# BareBonesArduino.net
KiCad netlist of a schematic drawn in EAGLE
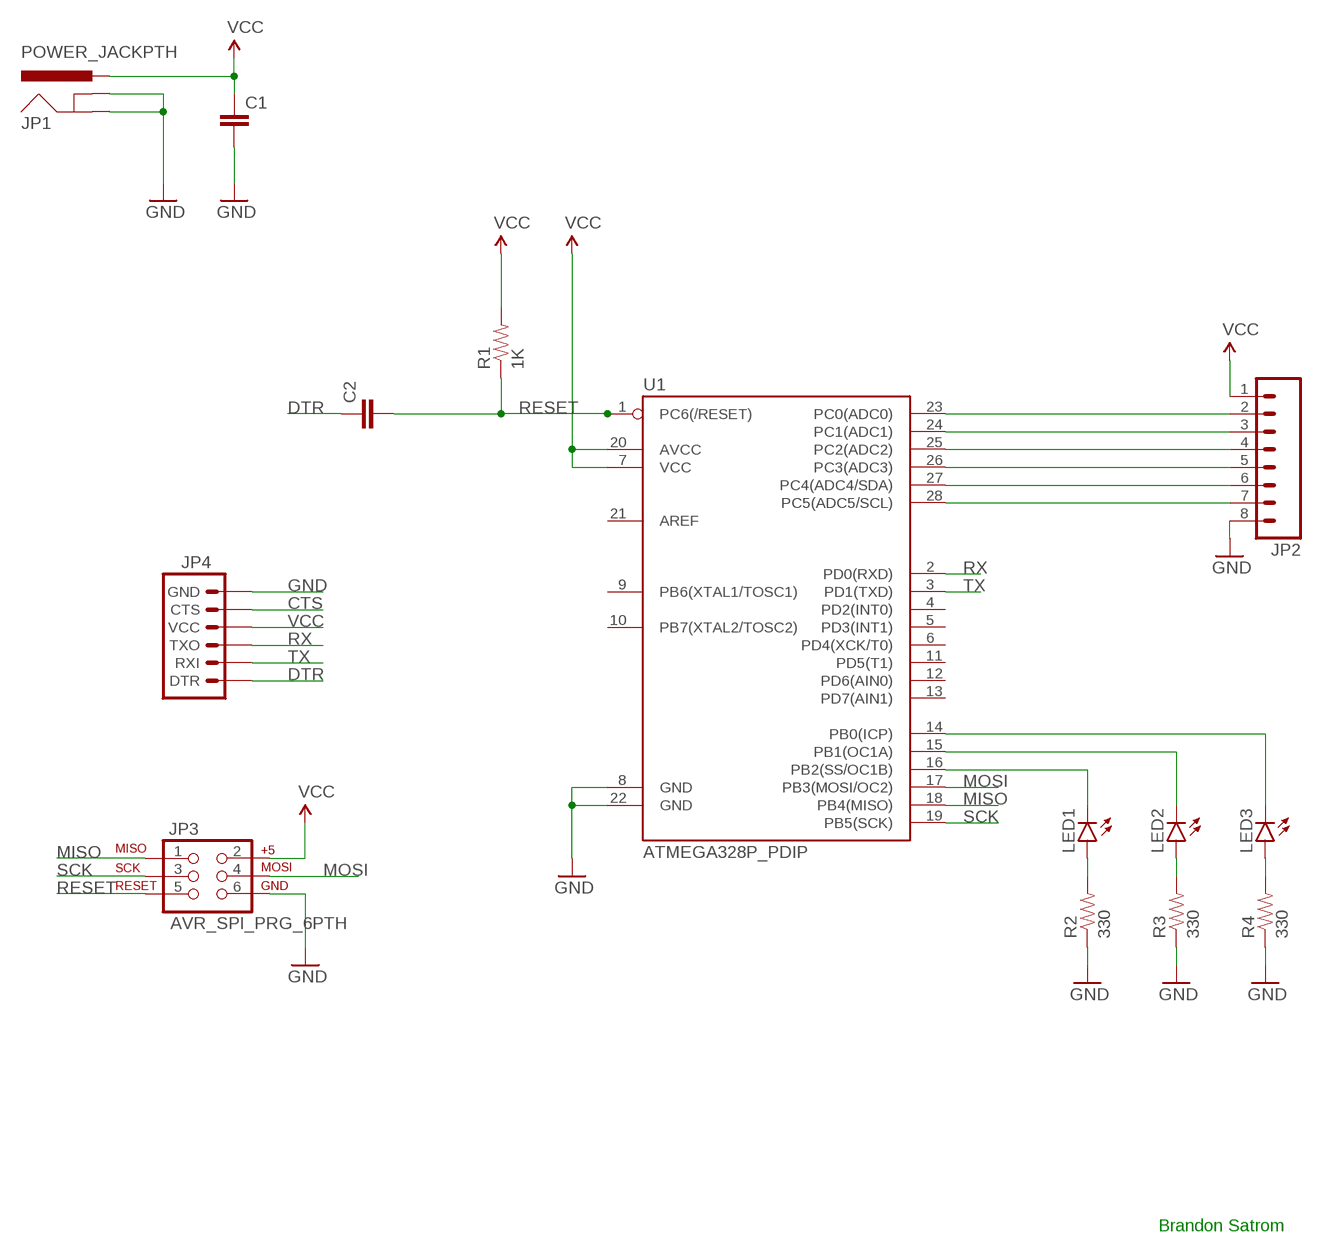
[diagram p0: schematic, sheet 1]

(export (version "E")
  (design (tool "Eeschema 10.0.6"))
  (components
    (comp (ref "C1")
      (value "CAPPTH")
      (footprint "eagle-import:CAP-PTH-SMALL")
      (libsource (lib "eagle-import") (part "CAPPTH"))
    )
    (comp (ref "C2")
      (value "CAPPTH")
      (footprint "eagle-import:CAP-PTH-SMALL")
      (libsource (lib "eagle-import") (part "CAPPTH"))
    )
    (comp (ref "JP1")
      (value "POWER_JACKPTH")
      (footprint "eagle-import:POWER_JACK_PTH")
      (libsource (lib "eagle-import") (part "POWER_JACKPTH"))
    )
    (comp (ref "JP2")
      (value "M08")
      (footprint "eagle-import:1X08_ROUND")
      (libsource (lib "eagle-import") (part "M08"))
    )
    (comp (ref "JP3")
      (value "AVR_SPI_PRG_6PTH")
      (footprint "eagle-import:2X3")
      (libsource (lib "eagle-import") (part "AVR_SPI_PRG_6PTH"))
    )
    (comp (ref "JP4")
      (value "ARDUINO_SERIAL_PROGRAMPTH")
      (footprint "eagle-import:1X06")
      (libsource (lib "eagle-import") (part "ARDUINO_SERIAL_PROGRAMPTH"))
    )
    (comp (ref "LED1")
      (value "LED5MM")
      (footprint "eagle-import:LED5MM")
      (libsource (lib "eagle-import") (part "LED5MM"))
    )
    (comp (ref "LED2")
      (value "LED5MM")
      (footprint "eagle-import:LED5MM")
      (libsource (lib "eagle-import") (part "LED5MM"))
    )
    (comp (ref "LED3")
      (value "LED5MM")
      (footprint "eagle-import:LED5MM")
      (libsource (lib "eagle-import") (part "LED5MM"))
    )
    (comp (ref "R1")
      (value "1K")
      (footprint "eagle-import:AXIAL-0.4")
      (libsource (lib "eagle-import") (part "RESISTORPTH-1/4W"))
    )
    (comp (ref "R2")
      (value "330")
      (footprint "eagle-import:AXIAL-0.4")
      (libsource (lib "eagle-import") (part "RESISTORPTH-1/4W"))
    )
    (comp (ref "R3")
      (value "330")
      (footprint "eagle-import:AXIAL-0.4")
      (libsource (lib "eagle-import") (part "RESISTORPTH-1/4W"))
    )
    (comp (ref "R4")
      (value "330")
      (footprint "eagle-import:AXIAL-0.4")
      (libsource (lib "eagle-import") (part "RESISTORPTH-1/4W"))
    )
    (comp (ref "U1")
      (value "ATMEGA328P_PDIP")
      (footprint "eagle-import:DIL28-3")
      (libsource (lib "eagle-import") (part "ATMEGA328P_PDIP"))
    )
  )
  (nets
    (net (code "1") (name "/CTS") (class "Default")
      (node (ref "JP4") (pin "5") (pinfunction "CTS_5") (pintype "passive"))
    )
    (net (code "2") (name "/DTR") (class "Default")
      (node (ref "C2") (pin "1") (pinfunction "1_1") (pintype "passive"))
      (node (ref "JP4") (pin "1") (pinfunction "DTR_1") (pintype "passive"))
    )
    (net (code "3") (name "/MISO") (class "Default")
      (node (ref "JP3") (pin "1") (pinfunction "1_1") (pintype "passive"))
      (node (ref "U1") (pin "18") (pinfunction "PB4(MISO)_18") (pintype "bidirectional"))
    )
    (net (code "4") (name "/MOSI") (class "Default")
      (node (ref "JP3") (pin "4") (pinfunction "4_4") (pintype "passive"))
      (node (ref "U1") (pin "17") (pinfunction "PB3(MOSI/OC2)_17") (pintype "bidirectional"))
    )
    (net (code "5") (name "/RESET") (class "Default")
      (node (ref "C2") (pin "2") (pinfunction "2_2") (pintype "passive"))
      (node (ref "JP3") (pin "5") (pinfunction "5_5") (pintype "passive"))
      (node (ref "R1") (pin "P$1") (pinfunction "1_P$1") (pintype "passive"))
      (node (ref "U1") (pin "1") (pinfunction "PC6(/RESET)_1") (pintype "bidirectional"))
    )
    (net (code "6") (name "/RX") (class "Default")
      (node (ref "JP4") (pin "3") (pinfunction "TXO_3") (pintype "passive"))
      (node (ref "U1") (pin "2") (pinfunction "PD0(RXD)_2") (pintype "bidirectional"))
    )
    (net (code "7") (name "/SCK") (class "Default")
      (node (ref "JP3") (pin "3") (pinfunction "3_3") (pintype "passive"))
      (node (ref "U1") (pin "19") (pinfunction "PB5(SCK)_19") (pintype "bidirectional"))
    )
    (net (code "8") (name "/TX") (class "Default")
      (node (ref "JP4") (pin "2") (pinfunction "RXI_2") (pintype "passive"))
      (node (ref "U1") (pin "3") (pinfunction "PD1(TXD)_3") (pintype "bidirectional"))
    )
    (net (code "9") (name "GND") (class "Default")
      (node (ref "C1") (pin "2") (pinfunction "2_2") (pintype "passive"))
      (node (ref "JP1") (pin "GND") (pinfunction "GND_GND") (pintype "bidirectional"))
      (node (ref "JP1") (pin "GNDBREAK") (pinfunction "GNDBREAK_GNDBREAK") (pintype "bidirectional"))
      (node (ref "JP2") (pin "8") (pinfunction "8_8") (pintype "passive"))
      (node (ref "JP3") (pin "6") (pinfunction "6_6") (pintype "passive"))
      (node (ref "JP4") (pin "6") (pinfunction "GND_6") (pintype "passive"))
      (node (ref "R2") (pin "P$1") (pinfunction "1_P$1") (pintype "passive"))
      (node (ref "R3") (pin "P$1") (pinfunction "1_P$1") (pintype "passive"))
      (node (ref "R4") (pin "P$1") (pinfunction "1_P$1") (pintype "passive"))
      (node (ref "U1") (pin "22") (pinfunction "GND_22") (pintype "bidirectional"))
      (node (ref "U1") (pin "8") (pinfunction "GND_8") (pintype "bidirectional"))
    )
    (net (code "10") (name "Net-(LED1-C)") (class "Default")
      (node (ref "LED1") (pin "K") (pinfunction "C_K") (pintype "passive"))
      (node (ref "U1") (pin "16") (pinfunction "PB2(SS/OC1B)_16") (pintype "bidirectional"))
    )
    (net (code "11") (name "Net-(LED2-C)") (class "Default")
      (node (ref "LED2") (pin "K") (pinfunction "C_K") (pintype "passive"))
      (node (ref "U1") (pin "15") (pinfunction "PB1(OC1A)_15") (pintype "bidirectional"))
    )
    (net (code "12") (name "Net-(LED3-C)") (class "Default")
      (node (ref "LED3") (pin "K") (pinfunction "C_K") (pintype "passive"))
      (node (ref "U1") (pin "14") (pinfunction "PB0(ICP)_14") (pintype "bidirectional"))
    )
    (net (code "13") (name "Net-(R2-2)") (class "Default")
      (node (ref "LED1") (pin "A") (pinfunction "A_A") (pintype "passive"))
      (node (ref "R2") (pin "P$2") (pinfunction "2_P$2") (pintype "passive"))
    )
    (net (code "14") (name "Net-(R3-2)") (class "Default")
      (node (ref "LED2") (pin "A") (pinfunction "A_A") (pintype "passive"))
      (node (ref "R3") (pin "P$2") (pinfunction "2_P$2") (pintype "passive"))
    )
    (net (code "15") (name "Net-(R4-2)") (class "Default")
      (node (ref "LED3") (pin "A") (pinfunction "A_A") (pintype "passive"))
      (node (ref "R4") (pin "P$2") (pinfunction "2_P$2") (pintype "passive"))
    )
    (net (code "16") (name "Net-(U1-PC0(ADC0))") (class "Default")
      (node (ref "JP2") (pin "2") (pinfunction "2_2") (pintype "passive"))
      (node (ref "U1") (pin "23") (pinfunction "PC0(ADC0)_23") (pintype "bidirectional"))
    )
    (net (code "17") (name "Net-(U1-PC1(ADC1))") (class "Default")
      (node (ref "JP2") (pin "3") (pinfunction "3_3") (pintype "passive"))
      (node (ref "U1") (pin "24") (pinfunction "PC1(ADC1)_24") (pintype "bidirectional"))
    )
    (net (code "18") (name "Net-(U1-PC2(ADC2))") (class "Default")
      (node (ref "JP2") (pin "4") (pinfunction "4_4") (pintype "passive"))
      (node (ref "U1") (pin "25") (pinfunction "PC2(ADC2)_25") (pintype "bidirectional"))
    )
    (net (code "19") (name "Net-(U1-PC3(ADC3))") (class "Default")
      (node (ref "JP2") (pin "5") (pinfunction "5_5") (pintype "passive"))
      (node (ref "U1") (pin "26") (pinfunction "PC3(ADC3)_26") (pintype "bidirectional"))
    )
    (net (code "20") (name "Net-(U1-PC4(ADC4{slash}SDA))") (class "Default")
      (node (ref "JP2") (pin "6") (pinfunction "6_6") (pintype "passive"))
      (node (ref "U1") (pin "27") (pinfunction "PC4(ADC4/SDA)_27") (pintype "bidirectional"))
    )
    (net (code "21") (name "Net-(U1-PC5(ADC5{slash}SCL))") (class "Default")
      (node (ref "JP2") (pin "7") (pinfunction "7_7") (pintype "passive"))
      (node (ref "U1") (pin "28") (pinfunction "PC5(ADC5/SCL)_28") (pintype "bidirectional"))
    )
    (net (code "22") (name "VCC") (class "Default")
      (node (ref "C1") (pin "1") (pinfunction "1_1") (pintype "passive"))
      (node (ref "JP1") (pin "PWR") (pinfunction "PWR_PWR") (pintype "bidirectional"))
      (node (ref "JP2") (pin "1") (pinfunction "1_1") (pintype "passive"))
      (node (ref "JP3") (pin "2") (pinfunction "2_2") (pintype "passive"))
      (node (ref "JP4") (pin "4") (pinfunction "VCC_4") (pintype "passive"))
      (node (ref "R1") (pin "P$2") (pinfunction "2_P$2") (pintype "passive"))
      (node (ref "U1") (pin "20") (pinfunction "AVCC_20") (pintype "bidirectional"))
      (node (ref "U1") (pin "7") (pinfunction "VCC_7") (pintype "bidirectional"))
    )
    (net (code "23") (name "unconnected-(U1-AREF-Pad21)") (class "Default")
      (node (ref "U1") (pin "21") (pinfunction "AREF_21") (pintype "bidirectional"))
    )
    (net (code "24") (name "unconnected-(U1-PB6(XTAL1{slash}TOSC1)-Pad9)") (class "Default")
      (node (ref "U1") (pin "9") (pinfunction "PB6(XTAL1/TOSC1)_9") (pintype "bidirectional"))
    )
    (net (code "25") (name "unconnected-(U1-PB7(XTAL2{slash}TOSC2)-Pad10)") (class "Default")
      (node (ref "U1") (pin "10") (pinfunction "PB7(XTAL2/TOSC2)_10") (pintype "bidirectional"))
    )
    (net (code "26") (name "unconnected-(U1-PD2(INT0)-Pad4)") (class "Default")
      (node (ref "U1") (pin "4") (pinfunction "PD2(INT0)_4") (pintype "bidirectional"))
    )
    (net (code "27") (name "unconnected-(U1-PD3(INT1)-Pad5)") (class "Default")
      (node (ref "U1") (pin "5") (pinfunction "PD3(INT1)_5") (pintype "bidirectional"))
    )
    (net (code "28") (name "unconnected-(U1-PD4(XCK{slash}T0)-Pad6)") (class "Default")
      (node (ref "U1") (pin "6") (pinfunction "PD4(XCK/T0)_6") (pintype "bidirectional"))
    )
    (net (code "29") (name "unconnected-(U1-PD5(T1)-Pad11)") (class "Default")
      (node (ref "U1") (pin "11") (pinfunction "PD5(T1)_11") (pintype "bidirectional"))
    )
    (net (code "30") (name "unconnected-(U1-PD6(AIN0)-Pad12)") (class "Default")
      (node (ref "U1") (pin "12") (pinfunction "PD6(AIN0)_12") (pintype "bidirectional"))
    )
    (net (code "31") (name "unconnected-(U1-PD7(AIN1)-Pad13)") (class "Default")
      (node (ref "U1") (pin "13") (pinfunction "PD7(AIN1)_13") (pintype "bidirectional"))
    )
  )
)
